# robotic_arm_arduino_uno_shield_smd.net
KiCad netlist of a schematic drawn in EAGLE
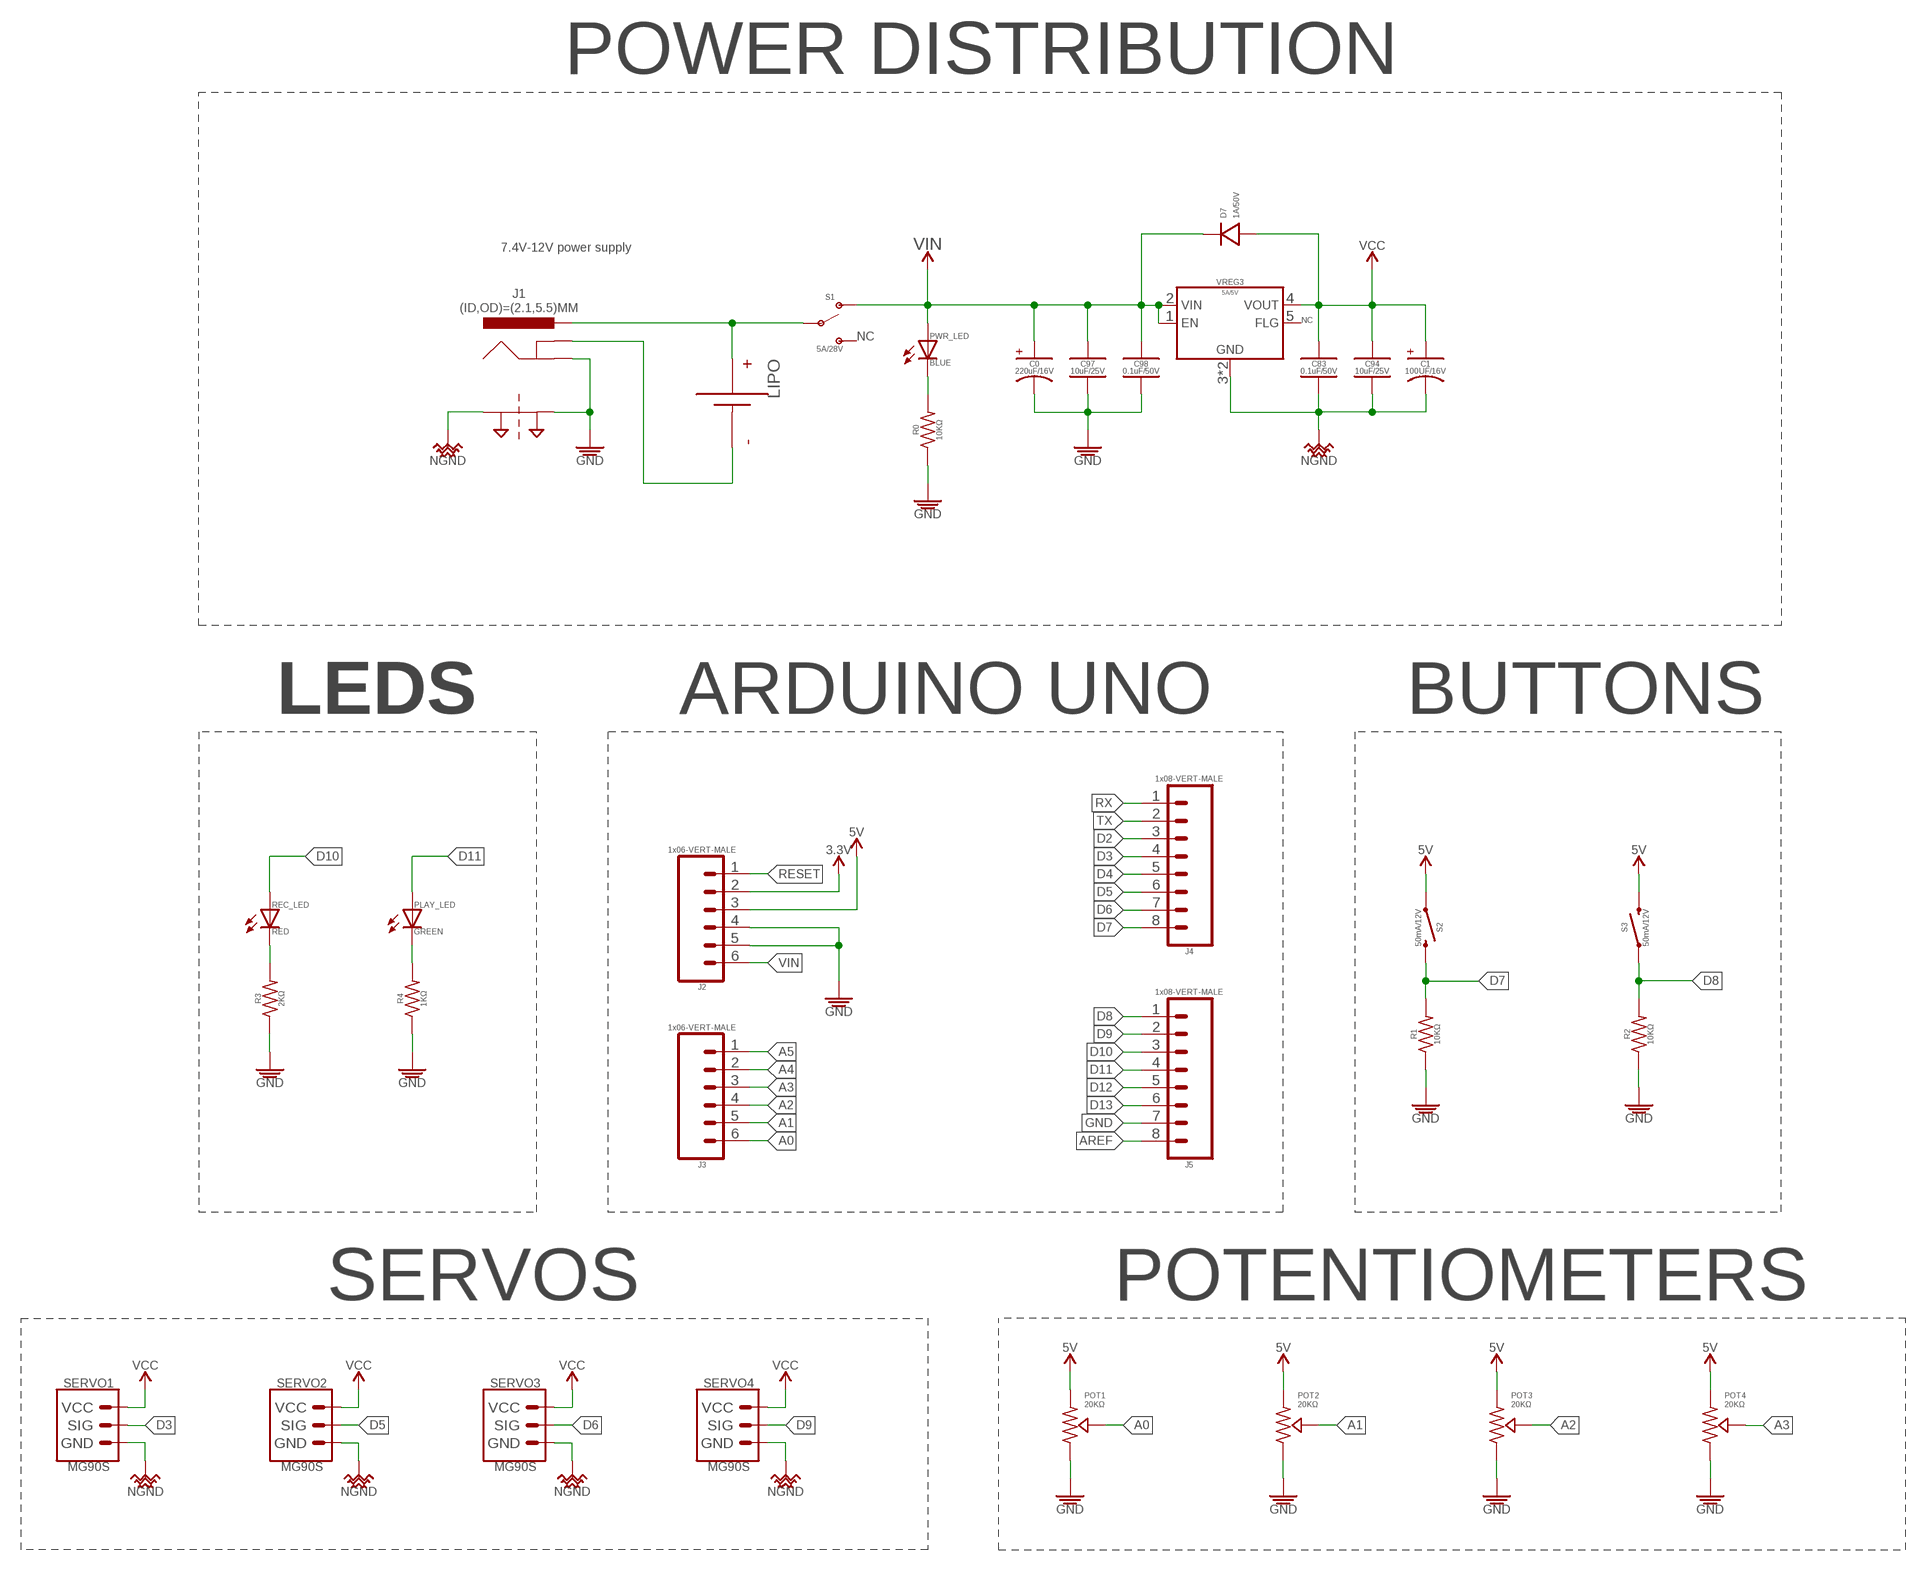
[diagram p0: schematic, sheet 1]

(export (version "E")
  (design (tool "Eeschema 10.0.6"))
  (components
    (comp (ref "C0")
      (value "220uF/16V")
      (footprint "eagle-import:CAP_POL_SMD_L6.6-W6.6")
      (fields
        (field (name "MFR") "Panasonic Electronic Components")
        (field (name "MPN") "EEE-FT1C221AP")
        (field (name "CREATOR") "MrSwirlyEyes")
      )
      (libsource (lib "eagle-import") (part "CAP_POLARIZED_ALUM-ELECTROLYTIC_SMD_220UF-16V-20%"))
    )
    (comp (ref "C1")
      (value "100UF/16V")
      (footprint "eagle-import:CAP_POL_SMD_L6.6-W6.6")
      (fields
        (field (name "MFR") "Panasonic Electronic Components")
        (field (name "MPN") "EEE-FK1C101P")
        (field (name "CREATOR") "MrSwirlyEyes")
      )
      (libsource (lib "eagle-import") (part "CAP_POLARIZED_ALUM-ELECTROLYTIC_SMD_100UF-16V-20%"))
    )
    (comp (ref "C83")
      (value "0.1uF/50V")
      (footprint "eagle-import:CAP_CER_SMD-805")
      (fields
        (field (name "MFR") "Murata Electronics North America")
        (field (name "MPN") "GRM21BR71H104KA01L")
        (field (name "CREATOR") "MrSwirlyEyes")
      )
      (libsource (lib "eagle-import") (part "CAP_CERAMIC_SMD-805_0.1UF-50V-10%"))
    )
    (comp (ref "C94")
      (value "10uF/25V")
      (footprint "eagle-import:CAP_CER_SMD-805")
      (fields
        (field (name "MFR") "Murata Electronics North America")
        (field (name "MPN") "GRM21BR61E106KA73L")
        (field (name "CREATOR") "MrSwirlyEyes")
      )
      (libsource (lib "eagle-import") (part "CAP_CERAMIC_SMD-805_10UF-25V-10%"))
    )
    (comp (ref "C97")
      (value "10uF/25V")
      (footprint "eagle-import:CAP_CER_SMD-805")
      (fields
        (field (name "MFR") "Murata Electronics North America")
        (field (name "MPN") "GRM21BR61E106KA73L")
        (field (name "CREATOR") "MrSwirlyEyes")
      )
      (libsource (lib "eagle-import") (part "CAP_CERAMIC_SMD-805_10UF-25V-10%"))
    )
    (comp (ref "C98")
      (value "0.1uF/50V")
      (footprint "eagle-import:CAP_CER_SMD-805")
      (fields
        (field (name "MFR") "Murata Electronics North America")
        (field (name "MPN") "GRM21BR71H104KA01L")
        (field (name "CREATOR") "MrSwirlyEyes")
      )
      (libsource (lib "eagle-import") (part "CAP_CERAMIC_SMD-805_0.1UF-50V-10%"))
    )
    (comp (ref "D7")
      (value "1A/50V")
      (footprint "eagle-import:DIODE_SMD_1A-50V-SOD123F")
      (fields
        (field (name "MFR") "Comchip Technology")
        (field (name "MPN") "CGRKM4001-HF")
        (field (name "CREATOR") "MrSwirlyEyes")
      )
      (libsource (lib "eagle-import") (part "DIODE_GEN-PURPSMD_GP_1A-50V-SOD123F"))
    )
    (comp (ref "J1")
      (value "(ID,OD)=(2.1,5.5)MM")
      (footprint "eagle-import:POWER_JACK_SLOT_ID2.1MM-OD5.5MM")
      (fields
        (field (name "MFR") "MPD (Memory Protection Devices)")
        (field (name "MPN") "EJ508A")
        (field (name "CREATOR") "MrSwirlyEyes")
      )
      (libsource (lib "eagle-import") (part "POWER_JACK-BARREL_ID2.1MM-OD5.5MM"))
    )
    (comp (ref "J2")
      (value "1x06-VERT-MALE")
      (footprint "eagle-import:1X06-VERT-MALE")
      (fields
        (field (name "MFR") "Sullins Connector Solutions")
        (field (name "MPN") "PEC06SAAN")
        (field (name "CREATOR") "MrSwirlyEyes")
      )
      (libsource (lib "eagle-import") (part "1X06VERT-MALE"))
    )
    (comp (ref "J3")
      (value "1x06-VERT-MALE")
      (footprint "eagle-import:1X06-VERT-MALE")
      (fields
        (field (name "MFR") "Sullins Connector Solutions")
        (field (name "MPN") "PEC06SAAN")
        (field (name "CREATOR") "MrSwirlyEyes")
      )
      (libsource (lib "eagle-import") (part "1X06VERT-MALE"))
    )
    (comp (ref "J4")
      (value "1x08-VERT-MALE")
      (footprint "eagle-import:1X08-VERT-MALE")
      (fields
        (field (name "MFR") "Sullins Connector Solutions")
        (field (name "MPN") "PEC08SAAN")
        (field (name "CREATOR") "MrSwirlyEyes")
      )
      (libsource (lib "eagle-import") (part "1X08VERT-MALE"))
    )
    (comp (ref "J5")
      (value "1x08-VERT-MALE")
      (footprint "eagle-import:1X08-VERT-MALE")
      (fields
        (field (name "MFR") "Sullins Connector Solutions")
        (field (name "MPN") "PEC08SAAN")
        (field (name "CREATOR") "MrSwirlyEyes")
      )
      (libsource (lib "eagle-import") (part "1X08VERT-MALE"))
    )
    (comp (ref "LIPO")
      (value "BATTERYPTH_HOLES")
      (footprint "eagle-import:DUAL_PTH_PADS")
      (libsource (lib "eagle-import") (part "BATTERYPTH_HOLES"))
    )
    (comp (ref "PLAY_LED")
      (value "GREEN")
      (footprint "eagle-import:LED_SMD-805_")
      (fields
        (field (name "MFR") "Lite-On Inc.")
        (field (name "MPN") "LTST-C170KGKT")
        (field (name "CREATOR") "MrSwirlyEyes")
      )
      (libsource (lib "eagle-import") (part "LED_SMD-805_DISCRETE_GREEN"))
    )
    (comp (ref "POT1")
      (value "20KΩ")
      (footprint "eagle-import:CONNECTOR_POTENTIOMETER_NO-MARKINGS_FEMALE-HEADER")
      (fields
        (field (name "MFR") "Bourns Inc.")
        (field (name "MPN") "PDB181-K420K-203B")
        (field (name "CREATOR") "MrSwirlyEyes")
      )
      (libsource (lib "eagle-import") (part "POTENTIOMETERNO-MARKINGS_VERT-FEMALE"))
    )
    (comp (ref "POT2")
      (value "20KΩ")
      (footprint "eagle-import:CONNECTOR_POTENTIOMETER_NO-MARKINGS_FEMALE-HEADER")
      (fields
        (field (name "MFR") "Bourns Inc.")
        (field (name "MPN") "PDB181-K420K-203B")
        (field (name "CREATOR") "MrSwirlyEyes")
      )
      (libsource (lib "eagle-import") (part "POTENTIOMETERNO-MARKINGS_VERT-FEMALE"))
    )
    (comp (ref "POT3")
      (value "20KΩ")
      (footprint "eagle-import:CONNECTOR_POTENTIOMETER_NO-MARKINGS_FEMALE-HEADER")
      (fields
        (field (name "MFR") "Bourns Inc.")
        (field (name "MPN") "PDB181-K420K-203B")
        (field (name "CREATOR") "MrSwirlyEyes")
      )
      (libsource (lib "eagle-import") (part "POTENTIOMETERNO-MARKINGS_VERT-FEMALE"))
    )
    (comp (ref "POT4")
      (value "20KΩ")
      (footprint "eagle-import:CONNECTOR_POTENTIOMETER_NO-MARKINGS_FEMALE-HEADER")
      (fields
        (field (name "MFR") "Bourns Inc.")
        (field (name "MPN") "PDB181-K420K-203B")
        (field (name "CREATOR") "MrSwirlyEyes")
      )
      (libsource (lib "eagle-import") (part "POTENTIOMETERNO-MARKINGS_VERT-FEMALE"))
    )
    (comp (ref "PWR_LED")
      (value "BLUE")
      (footprint "eagle-import:LED_SMD-805_")
      (fields
        (field (name "MFR") "Lite-On Inc.")
        (field (name "MPN") "LTST-C170TBKT")
        (field (name "CREATOR") "MrSwirlyEyes")
      )
      (libsource (lib "eagle-import") (part "LED_SMD-805_DISCRETE_BLUE"))
    )
    (comp (ref "R0")
      (value "10KΩ")
      (footprint "eagle-import:RESISTOR_SMD-805")
      (fields
        (field (name "MFR") "Yageo")
        (field (name "MPN") "RC0805JR-0710KL")
        (field (name "CREATOR") "Kenmei")
      )
      (libsource (lib "eagle-import") (part "RESISTORSMD-0805_1/8W_10K_5%"))
    )
    (comp (ref "R1")
      (value "10KΩ")
      (footprint "eagle-import:RESISTOR_SMD-805")
      (fields
        (field (name "MFR") "Yageo")
        (field (name "MPN") "RC0805JR-0710KL")
        (field (name "CREATOR") "Kenmei")
      )
      (libsource (lib "eagle-import") (part "RESISTORSMD-0805_1/8W_10K_5%"))
    )
    (comp (ref "R2")
      (value "10KΩ")
      (footprint "eagle-import:RESISTOR_SMD-805")
      (fields
        (field (name "MFR") "Yageo")
        (field (name "MPN") "RC0805JR-0710KL")
        (field (name "CREATOR") "Kenmei")
      )
      (libsource (lib "eagle-import") (part "RESISTORSMD-0805_1/8W_10K_5%"))
    )
    (comp (ref "R3")
      (value "2KΩ")
      (footprint "eagle-import:RESISTOR_SMD-805")
      (fields
        (field (name "MFR") "Yageo")
        (field (name "MPN") "RC0805JR-072KL")
        (field (name "CREATOR") "MrSwirlyEyes")
      )
      (libsource (lib "eagle-import") (part "RESISTORSMD-0805_1/8W_2K_5%"))
    )
    (comp (ref "R4")
      (value "1KΩ")
      (footprint "eagle-import:RESISTOR_SMD-805")
      (fields
        (field (name "MFR") "Yageo")
        (field (name "MPN") "RC0805JR-071KL ")
        (field (name "CREATOR") "Kenmei")
      )
      (libsource (lib "eagle-import") (part "RESISTORSMD-0805_1/8W_1K_5%"))
    )
    (comp (ref "REC_LED")
      (value "RED")
      (footprint "eagle-import:LED_SMD-805_")
      (fields
        (field (name "MFR") "Lite-On Inc.")
        (field (name "MPN") "LTST-C170KRKT")
        (field (name "CREATOR") "MrSwirlyEyes")
      )
      (libsource (lib "eagle-import") (part "LED_SMD-805_DISCRETE_RED"))
    )
    (comp (ref "S1")
      (value "5A/28V")
      (footprint "eagle-import:SW-SLIDE_SPDT_5A-28V_13L-7W")
      (fields
        (field (name "MFR") "E-Switch")
        (field (name "MPN") "100SP1T1B4M2QE")
        (field (name "CREATOR") "MrSwirlyEyes")
      )
      (libsource (lib "eagle-import") (part "SWITCH_SPDT5A-28V_13L-7W"))
    )
    (comp (ref "S2")
      (value "50mA/12V")
      (footprint "eagle-import:SPST-PTH-12MM")
      (fields (field (name "CREATOR") "MrSwirlyEyes"))
      (libsource (lib "eagle-import") (part "SWITCH_MOMENTARY_SPSTSPST-PTH-L12-W12-H7.2"))
    )
    (comp (ref "S3")
      (value "50mA/12V")
      (footprint "eagle-import:SPST-PTH-12MM")
      (fields (field (name "CREATOR") "MrSwirlyEyes"))
      (libsource (lib "eagle-import") (part "SWITCH_MOMENTARY_SPSTSPST-PTH-L12-W12-H7.2"))
    )
    (comp (ref "SERVO1")
      (value "MG90S")
      (footprint "eagle-import:CONNECTOR_SERVO_NO-MARKINGS")
      (fields (field (name "MFR") "TowerPro") (field (name "CREATOR") "MrSwirlyEyes"))
      (libsource (lib "eagle-import") (part "SERVOMG90S_NO-MARKINGS"))
    )
    (comp (ref "SERVO2")
      (value "MG90S")
      (footprint "eagle-import:CONNECTOR_SERVO_NO-MARKINGS")
      (fields (field (name "MFR") "TowerPro") (field (name "CREATOR") "MrSwirlyEyes"))
      (libsource (lib "eagle-import") (part "SERVOMG90S_NO-MARKINGS"))
    )
    (comp (ref "SERVO3")
      (value "MG90S")
      (footprint "eagle-import:CONNECTOR_SERVO_NO-MARKINGS")
      (fields (field (name "MFR") "TowerPro") (field (name "CREATOR") "MrSwirlyEyes"))
      (libsource (lib "eagle-import") (part "SERVOMG90S_NO-MARKINGS"))
    )
    (comp (ref "SERVO4")
      (value "MG90S")
      (footprint "eagle-import:CONNECTOR_SERVO_NO-MARKINGS")
      (fields (field (name "MFR") "TowerPro") (field (name "CREATOR") "MrSwirlyEyes"))
      (libsource (lib "eagle-import") (part "SERVOMG90S_NO-MARKINGS"))
    )
    (comp (ref "SUPPLY14")
      (value "2PT_GND_TIE")
      (footprint "eagle-import:2PT_GND_TIE")
      (libsource (lib "eagle-import") (part "2PT_GND_TIE"))
    )
    (comp (ref "VREG3")
      (value "5A/5V")
      (footprint "eagle-import:TO-263-5")
      (fields
        (field (name "MFR") "Microchip Technology")
        (field (name "MPN") "MIC29501-5.0WU")
        (field (name "CREATOR") "MrSwirlyEyes")
      )
      (libsource (lib "eagle-import") (part "VREG_MIC29501-5.0_LINEAR_ULDO_5A-5VMIC29501-5.0_5A-5V"))
    )
  )
  (nets
    (net (code "1") (name "3.3V") (class "Default")
      (node (ref "J2") (pin "2") (pinfunction "2_2") (pintype "passive"))
    )
    (net (code "2") (name "5V") (class "Default")
      (node (ref "J2") (pin "3") (pinfunction "3_3") (pintype "passive"))
      (node (ref "POT1") (pin "CCW") (pinfunction "CCW_CCW") (pintype "passive"))
      (node (ref "POT2") (pin "CCW") (pinfunction "CCW_CCW") (pintype "passive"))
      (node (ref "POT3") (pin "CCW") (pinfunction "CCW_CCW") (pintype "passive"))
      (node (ref "POT4") (pin "CCW") (pinfunction "CCW_CCW") (pintype "passive"))
      (node (ref "S2") (pin "1") (pinfunction "1_1") (pintype "passive"))
      (node (ref "S3") (pin "3") (pinfunction "2_3") (pintype "passive"))
    )
    (net (code "3") (name "A0") (class "Default")
      (node (ref "J3") (pin "6") (pinfunction "6_6") (pintype "passive"))
      (node (ref "POT1") (pin "S") (pinfunction "S_S") (pintype "passive"))
    )
    (net (code "4") (name "A1") (class "Default")
      (node (ref "J3") (pin "5") (pinfunction "5_5") (pintype "passive"))
      (node (ref "POT2") (pin "S") (pinfunction "S_S") (pintype "passive"))
    )
    (net (code "5") (name "A2") (class "Default")
      (node (ref "J3") (pin "4") (pinfunction "4_4") (pintype "passive"))
      (node (ref "POT3") (pin "S") (pinfunction "S_S") (pintype "passive"))
    )
    (net (code "6") (name "A3") (class "Default")
      (node (ref "J3") (pin "3") (pinfunction "3_3") (pintype "passive"))
      (node (ref "POT4") (pin "S") (pinfunction "S_S") (pintype "passive"))
    )
    (net (code "7") (name "A4") (class "Default")
      (node (ref "J3") (pin "2") (pinfunction "2_2") (pintype "passive"))
    )
    (net (code "8") (name "A5") (class "Default")
      (node (ref "J3") (pin "1") (pinfunction "1_1") (pintype "passive"))
    )
    (net (code "9") (name "AREF") (class "Default")
      (node (ref "J5") (pin "8") (pinfunction "8_8") (pintype "passive"))
    )
    (net (code "10") (name "D2") (class "Default")
      (node (ref "J4") (pin "3") (pinfunction "3_3") (pintype "passive"))
    )
    (net (code "11") (name "D3") (class "Default")
      (node (ref "J4") (pin "4") (pinfunction "4_4") (pintype "passive"))
      (node (ref "SERVO1") (pin "1") (pinfunction "SIG_1") (pintype "passive"))
    )
    (net (code "12") (name "D4") (class "Default")
      (node (ref "J4") (pin "5") (pinfunction "5_5") (pintype "passive"))
    )
    (net (code "13") (name "D5") (class "Default")
      (node (ref "J4") (pin "6") (pinfunction "6_6") (pintype "passive"))
      (node (ref "SERVO2") (pin "1") (pinfunction "SIG_1") (pintype "passive"))
    )
    (net (code "14") (name "D6") (class "Default")
      (node (ref "J4") (pin "7") (pinfunction "7_7") (pintype "passive"))
      (node (ref "SERVO3") (pin "1") (pinfunction "SIG_1") (pintype "passive"))
    )
    (net (code "15") (name "D7") (class "Default")
      (node (ref "J4") (pin "8") (pinfunction "8_8") (pintype "passive"))
      (node (ref "R1") (pin "2") (pinfunction "2_2") (pintype "passive"))
      (node (ref "S2") (pin "3") (pinfunction "2_3") (pintype "passive"))
    )
    (net (code "16") (name "D8") (class "Default")
      (node (ref "J5") (pin "1") (pinfunction "1_1") (pintype "passive"))
      (node (ref "R2") (pin "2") (pinfunction "2_2") (pintype "passive"))
      (node (ref "S3") (pin "1") (pinfunction "1_1") (pintype "passive"))
    )
    (net (code "17") (name "D9") (class "Default")
      (node (ref "J5") (pin "2") (pinfunction "2_2") (pintype "passive"))
      (node (ref "SERVO4") (pin "1") (pinfunction "SIG_1") (pintype "passive"))
    )
    (net (code "18") (name "D10") (class "Default")
      (node (ref "J5") (pin "3") (pinfunction "3_3") (pintype "passive"))
      (node (ref "REC_LED") (pin "A") (pinfunction "A_A") (pintype "passive"))
    )
    (net (code "19") (name "D11") (class "Default")
      (node (ref "J5") (pin "4") (pinfunction "4_4") (pintype "passive"))
      (node (ref "PLAY_LED") (pin "A") (pinfunction "A_A") (pintype "passive"))
    )
    (net (code "20") (name "D12") (class "Default")
      (node (ref "J5") (pin "5") (pinfunction "5_5") (pintype "passive"))
    )
    (net (code "21") (name "D13") (class "Default")
      (node (ref "J5") (pin "6") (pinfunction "6_6") (pintype "passive"))
    )
    (net (code "22") (name "GND") (class "Default")
      (node (ref "C0") (pin "K") (pinfunction "K_K") (pintype "passive"))
      (node (ref "C97") (pin "2") (pinfunction "2_2") (pintype "passive"))
      (node (ref "C98") (pin "2") (pinfunction "2_2") (pintype "passive"))
      (node (ref "J1") (pin "GND@1") (pinfunction "GND_GND@1") (pintype "bidirectional"))
      (node (ref "J2") (pin "4") (pinfunction "4_4") (pintype "passive"))
      (node (ref "J2") (pin "5") (pinfunction "5_5") (pintype "passive"))
      (node (ref "J5") (pin "7") (pinfunction "7_7") (pintype "passive"))
      (node (ref "POT1") (pin "CW") (pinfunction "CW_CW") (pintype "passive"))
      (node (ref "POT2") (pin "CW") (pinfunction "CW_CW") (pintype "passive"))
      (node (ref "POT3") (pin "CW") (pinfunction "CW_CW") (pintype "passive"))
      (node (ref "POT4") (pin "CW") (pinfunction "CW_CW") (pintype "passive"))
      (node (ref "R0") (pin "1") (pinfunction "1_1") (pintype "passive"))
      (node (ref "R1") (pin "1") (pinfunction "1_1") (pintype "passive"))
      (node (ref "R2") (pin "1") (pinfunction "1_1") (pintype "passive"))
      (node (ref "R3") (pin "1") (pinfunction "1_1") (pintype "passive"))
      (node (ref "R4") (pin "1") (pinfunction "1_1") (pintype "passive"))
      (node (ref "SUPPLY14") (pin "P$2") (pinfunction "P$2_P$2") (pintype "bidirectional"))
    )
    (net (code "23") (name "NGND") (class "Default")
      (node (ref "C1") (pin "K") (pinfunction "K_K") (pintype "passive"))
      (node (ref "C83") (pin "2") (pinfunction "2_2") (pintype "passive"))
      (node (ref "C94") (pin "2") (pinfunction "2_2") (pintype "passive"))
      (node (ref "SERVO1") (pin "3") (pinfunction "GND_3") (pintype "passive"))
      (node (ref "SERVO2") (pin "3") (pinfunction "GND_3") (pintype "passive"))
      (node (ref "SERVO3") (pin "3") (pinfunction "GND_3") (pintype "passive"))
      (node (ref "SERVO4") (pin "3") (pinfunction "GND_3") (pintype "passive"))
      (node (ref "SUPPLY14") (pin "P$1") (pinfunction "P$1_P$1") (pintype "bidirectional"))
      (node (ref "VREG3") (pin "3") (pinfunction "GND_3") (pintype "bidirectional"))
      (node (ref "VREG3") (pin "TAB") (pinfunction "GND_TAB") (pintype "bidirectional"))
    )
    (net (code "24") (name "Net-(LIPO-N)") (class "Default")
      (node (ref "J1") (pin "GND@2") (pinfunction "GND_GND@2") (pintype "bidirectional"))
      (node (ref "LIPO") (pin "-") (pinfunction "N_-") (pintype "bidirectional"))
    )
    (net (code "25") (name "Net-(LIPO-P)") (class "Default")
      (node (ref "J1") (pin "PWR") (pinfunction "PWR_PWR") (pintype "bidirectional"))
      (node (ref "LIPO") (pin "+") (pinfunction "P_+") (pintype "bidirectional"))
      (node (ref "S1") (pin "P$2") (pinfunction "P_P$2") (pintype "passive"))
    )
    (net (code "26") (name "Net-(PLAY_LED-PadK)") (class "Default")
      (node (ref "PLAY_LED") (pin "K") (pinfunction "K_K") (pintype "passive"))
      (node (ref "R4") (pin "2") (pinfunction "2_2") (pintype "passive"))
    )
    (net (code "27") (name "Net-(PWR_LED-PadK)") (class "Default")
      (node (ref "PWR_LED") (pin "K") (pinfunction "K_K") (pintype "passive"))
      (node (ref "R0") (pin "2") (pinfunction "2_2") (pintype "passive"))
    )
    (net (code "28") (name "Net-(R3-Pad2)") (class "Default")
      (node (ref "R3") (pin "2") (pinfunction "2_2") (pintype "passive"))
      (node (ref "REC_LED") (pin "K") (pinfunction "K_K") (pintype "passive"))
    )
    (net (code "29") (name "RESET") (class "Default")
      (node (ref "J2") (pin "1") (pinfunction "1_1") (pintype "passive"))
    )
    (net (code "30") (name "RX") (class "Default")
      (node (ref "J4") (pin "1") (pinfunction "1_1") (pintype "passive"))
    )
    (net (code "31") (name "TX") (class "Default")
      (node (ref "J4") (pin "2") (pinfunction "2_2") (pintype "passive"))
    )
    (net (code "32") (name "VCC") (class "Default")
      (node (ref "C1") (pin "A") (pinfunction "A_A") (pintype "passive"))
      (node (ref "C83") (pin "1") (pinfunction "1_1") (pintype "passive"))
      (node (ref "C94") (pin "1") (pinfunction "1_1") (pintype "passive"))
      (node (ref "D7") (pin "A") (pinfunction "A_A") (pintype "passive"))
      (node (ref "SERVO1") (pin "2") (pinfunction "VCC_2") (pintype "passive"))
      (node (ref "SERVO2") (pin "2") (pinfunction "VCC_2") (pintype "passive"))
      (node (ref "SERVO3") (pin "2") (pinfunction "VCC_2") (pintype "passive"))
      (node (ref "SERVO4") (pin "2") (pinfunction "VCC_2") (pintype "passive"))
      (node (ref "VREG3") (pin "4") (pinfunction "VOUT_4") (pintype "bidirectional"))
    )
    (net (code "33") (name "VIN") (class "Default")
      (node (ref "C0") (pin "A") (pinfunction "A_A") (pintype "passive"))
      (node (ref "C97") (pin "1") (pinfunction "1_1") (pintype "passive"))
      (node (ref "C98") (pin "1") (pinfunction "1_1") (pintype "passive"))
      (node (ref "D7") (pin "K") (pinfunction "K_K") (pintype "passive"))
      (node (ref "J2") (pin "6") (pinfunction "6_6") (pintype "passive"))
      (node (ref "PWR_LED") (pin "A") (pinfunction "A_A") (pintype "passive"))
      (node (ref "S1") (pin "P$1") (pinfunction "S1_P$1") (pintype "passive"))
      (node (ref "VREG3") (pin "1") (pinfunction "EN_1") (pintype "bidirectional"))
      (node (ref "VREG3") (pin "2") (pinfunction "VIN_2") (pintype "bidirectional"))
    )
    (net (code "34") (name "unconnected-(S1-S2-PadP$3)") (class "Default")
      (node (ref "S1") (pin "P$3") (pinfunction "S2_P$3") (pintype "passive"))
    )
    (net (code "35") (name "unconnected-(VREG3-FLG-Pad5)") (class "Default")
      (node (ref "VREG3") (pin "5") (pinfunction "FLG_5") (pintype "bidirectional"))
    )
  )
)
